# Pulser.net
KiCad netlist of a schematic drawn in Altium Designer
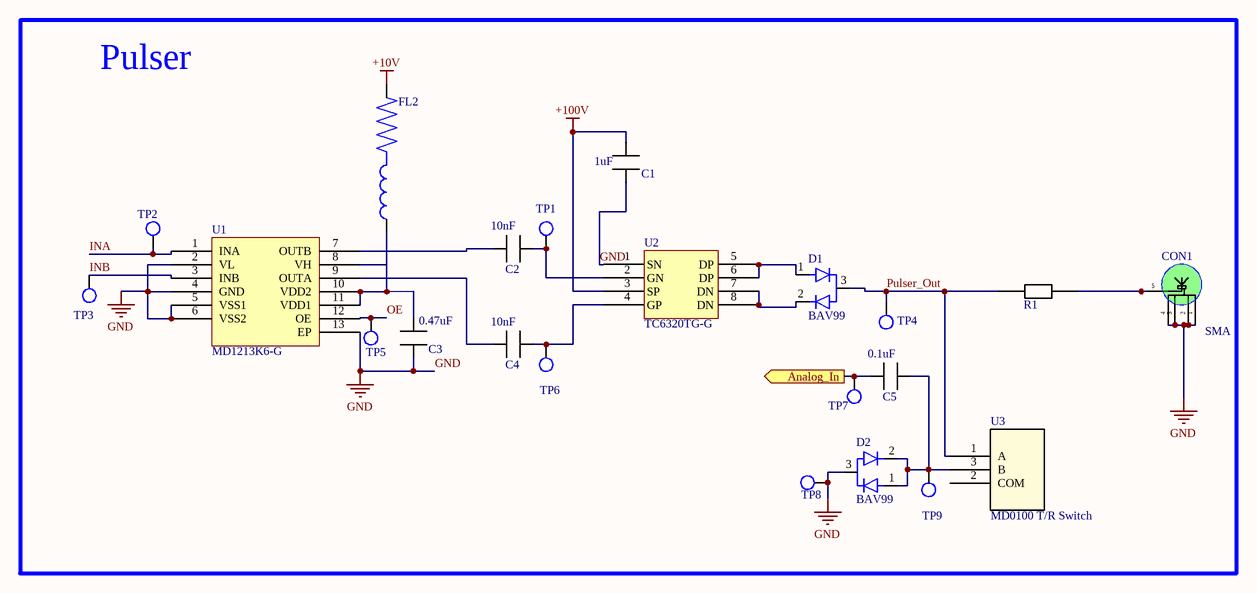
[diagram p0: Pulser.SchDoc]

(export (version "E")
  (design (tool "Eeschema 10.0.6"))
  (components
    (comp (ref "C1")
      (value "1uF")
      (footprint "CAP_1206")
      (description "CAP_1206")
      (fields (field (name "VAL") "1uF"))
      (libsource (lib "Passives") (part "CAP_1206"))
    )
    (comp (ref "C2")
      (value "10nF")
      (footprint "CAP_0805")
      (description "CAP_0805")
      (fields (field (name "VAL") "10nF"))
      (libsource (lib "Passives") (part "CAP_0805"))
    )
    (comp (ref "C3")
      (value "0.47uF")
      (footprint "CAP_0805")
      (description "CAP_0805")
      (fields (field (name "VAL") "0.47uF"))
      (libsource (lib "Passives") (part "CAP_0805"))
    )
    (comp (ref "C4")
      (value "10nF")
      (footprint "CAP_0805")
      (description "CAP_0805")
      (fields (field (name "VAL") "10nF"))
      (libsource (lib "Passives") (part "CAP_0805"))
    )
    (comp (ref "C5")
      (value "0.1uF")
      (footprint "CAP_0805")
      (description "CAP_0805")
      (fields (field (name "VAL") "0.1uF"))
      (libsource (lib "Passives") (part "CAP_0805"))
    )
    (comp (ref "CON1")
      (value "SMA")
      (footprint "A-SMA-KWE-15.1A")
      (libsource (lib "Connectors") (part "A-SMA-KWE-15.1A"))
    )
    (comp (ref "D1")
      (value "BAV99")
      (footprint "DIO_BAV99")
      (fields (field (name "MF") "ON Semiconductor"))
      (libsource (lib "Passives") (part "BAV99"))
    )
    (comp (ref "D2")
      (value "BAV99")
      (footprint "DIO_BAV99")
      (fields (field (name "MF") "ON Semiconductor"))
      (libsource (lib "Passives") (part "BAV99"))
    )
    (comp (ref "FL2")
      (value "~")
      (footprint "BEAD1206S601A40T")
      (fields (field (name "MF") "Murata") (field (name "MP") "BLM03EB500SZ1D"))
      (libsource (lib "Passives") (part "BEAD1206S601A40T"))
    )
    (comp (ref "R1")
      (value "200R")
      (footprint "RES_0805")
      (description "RES_0805")
      (libsource (lib "Passives") (part "RES_0805"))
    )
    (comp (ref "TP1") (value "TP") (footprint "CON_TP") (libsource (lib "Connectors") (part "Test_Point")))
    (comp (ref "TP2") (value "TP") (footprint "CON_TP") (libsource (lib "Connectors") (part "Test_Point")))
    (comp (ref "TP3") (value "TP") (footprint "CON_TP") (libsource (lib "Connectors") (part "Test_Point")))
    (comp (ref "TP4") (value "TP") (footprint "CON_TP") (libsource (lib "Connectors") (part "Test_Point")))
    (comp (ref "TP5") (value "TP") (footprint "CON_TP") (libsource (lib "Connectors") (part "Test_Point")))
    (comp (ref "TP6") (value "TP") (footprint "CON_TP") (libsource (lib "Connectors") (part "Test_Point")))
    (comp (ref "TP7") (value "TP") (footprint "CON_TP") (libsource (lib "Connectors") (part "Test_Point")))
    (comp (ref "TP8") (value "TP") (footprint "CON_TP") (libsource (lib "Connectors") (part "Test_Point")))
    (comp (ref "TP9") (value "TP") (footprint "CON_TP") (libsource (lib "Connectors") (part "Test_Point")))
    (comp (ref "U1")
      (value "MD1213K6-G")
      (footprint "QFN80P400X400X90-13N")
      (libsource (lib "IC_Digital") (part "MD1213K6-G"))
    )
    (comp (ref "U2")
      (value "TC6320TG-G")
      (footprint "SOIC127P600X175-8N")
      (libsource (lib "IC_Digital") (part "TC6320TG-G"))
    )
    (comp (ref "U3")
      (value "MD0100 T/R Switch")
      (footprint "TO-243AA_MCH")
      (description "Description")
      (fields
        (field (name "MANUFACTURER_PART_NUMBER") "MD0100N8-G")
        (field (name "COPYRIGHT") "Copyright (C) 2025 Ultra Librarian. All rights reserved.")
      )
      (libsource (lib "IC_Digital") (part "MD0100N8-G"))
    )
  )
  (nets
    (net (code "1") (name "+10V") (class "Default")
      (node (ref "FL2") (pin "2") (pinfunction "2_2") (pintype "passive"))
    )
    (net (code "2") (name "+100V") (class "Default")
      (node (ref "C1") (pin "2") (pinfunction "2_2") (pintype "passive"))
      (node (ref "U2") (pin "3") (pinfunction "SP_3") (pintype "passive"))
    )
    (net (code "3") (name "/Analog_In") (class "Default")
      (node (ref "C5") (pin "1") (pinfunction "1_1") (pintype "passive"))
      (node (ref "TP7") (pin "1") (pinfunction "A1_1") (pintype "passive"))
    )
    (net (code "4") (name "/INA") (class "Default")
      (node (ref "TP2") (pin "1") (pinfunction "A1_1") (pintype "passive"))
      (node (ref "U1") (pin "1") (pinfunction "INA_1") (pintype "passive"))
    )
    (net (code "5") (name "/INB") (class "Default")
      (node (ref "TP3") (pin "1") (pinfunction "A1_1") (pintype "passive"))
      (node (ref "U1") (pin "3") (pinfunction "INB_3") (pintype "passive"))
    )
    (net (code "6") (name "/OE") (class "Default")
      (node (ref "TP5") (pin "1") (pinfunction "A1_1") (pintype "passive"))
      (node (ref "U1") (pin "12") (pinfunction "OE_12") (pintype "passive"))
    )
    (net (code "7") (name "/Pulser_Out") (class "Default")
      (node (ref "D1") (pin "3") (pinfunction "3_3") (pintype "passive"))
      (node (ref "R1") (pin "1") (pinfunction "1_1") (pintype "passive"))
      (node (ref "TP4") (pin "1") (pinfunction "A1_1") (pintype "passive"))
      (node (ref "U3") (pin "1") (pinfunction "A_1") (pintype "passive"))
    )
    (net (code "8") (name "GND") (class "Default")
      (node (ref "C1") (pin "1") (pinfunction "1_1") (pintype "passive"))
      (node (ref "C3") (pin "2") (pinfunction "2_2") (pintype "passive"))
      (node (ref "CON1") (pin "1") (pinfunction "1_1") (pintype "passive"))
      (node (ref "CON1") (pin "2") (pinfunction "2_2") (pintype "passive"))
      (node (ref "CON1") (pin "3") (pinfunction "3_3") (pintype "passive"))
      (node (ref "CON1") (pin "4") (pinfunction "4_4") (pintype "passive"))
      (node (ref "D2") (pin "3") (pinfunction "3_3") (pintype "passive"))
      (node (ref "TP8") (pin "1") (pinfunction "A1_1") (pintype "passive"))
      (node (ref "U1") (pin "13") (pinfunction "EP_13") (pintype "power_in"))
      (node (ref "U1") (pin "2") (pinfunction "VL_2") (pintype "passive"))
      (node (ref "U1") (pin "4") (pinfunction "GND_4") (pintype "passive"))
      (node (ref "U1") (pin "5") (pinfunction "VSS1_5") (pintype "passive"))
      (node (ref "U1") (pin "6") (pinfunction "VSS2_6") (pintype "passive"))
      (node (ref "U2") (pin "1") (pinfunction "SN_1") (pintype "passive"))
    )
    (net (code "9") (name "Net-(CON1-Pad5)") (class "Default")
      (node (ref "CON1") (pin "5") (pinfunction "5_5") (pintype "passive"))
      (node (ref "R1") (pin "2") (pinfunction "2_2") (pintype "passive"))
    )
    (net (code "10") (name "Net-(D1-Pad1)") (class "Default")
      (node (ref "D1") (pin "1") (pinfunction "1_1") (pintype "passive"))
      (node (ref "U2") (pin "5") (pinfunction "DP_5") (pintype "passive"))
      (node (ref "U2") (pin "6") (pinfunction "DP_6") (pintype "passive"))
    )
    (net (code "11") (name "Net-(D1-Pad2)") (class "Default")
      (node (ref "D1") (pin "2") (pinfunction "2_2") (pintype "passive"))
      (node (ref "U2") (pin "7") (pinfunction "DN_7") (pintype "passive"))
      (node (ref "U2") (pin "8") (pinfunction "DN_8") (pintype "passive"))
    )
    (net (code "12") (name "Net-(TP1-A1)") (class "Default")
      (node (ref "C2") (pin "2") (pinfunction "2_2") (pintype "passive"))
      (node (ref "TP1") (pin "1") (pinfunction "A1_1") (pintype "passive"))
      (node (ref "U2") (pin "2") (pinfunction "GN_2") (pintype "passive"))
    )
    (net (code "13") (name "Net-(TP6-A1)") (class "Default")
      (node (ref "C4") (pin "2") (pinfunction "2_2") (pintype "passive"))
      (node (ref "TP6") (pin "1") (pinfunction "A1_1") (pintype "passive"))
      (node (ref "U2") (pin "4") (pinfunction "GP_4") (pintype "passive"))
    )
    (net (code "14") (name "Net-(TP9-A1)") (class "Default")
      (node (ref "C5") (pin "2") (pinfunction "2_2") (pintype "passive"))
      (node (ref "D2") (pin "1") (pinfunction "1_1") (pintype "passive"))
      (node (ref "D2") (pin "2") (pinfunction "2_2") (pintype "passive"))
      (node (ref "TP9") (pin "1") (pinfunction "A1_1") (pintype "passive"))
      (node (ref "U3") (pin "3") (pinfunction "B_3") (pintype "passive"))
    )
    (net (code "15") (name "Net-(U1-OUTA)") (class "Default")
      (node (ref "C4") (pin "1") (pinfunction "1_1") (pintype "passive"))
      (node (ref "U1") (pin "9") (pinfunction "OUTA_9") (pintype "passive"))
    )
    (net (code "16") (name "Net-(U1-OUTB)") (class "Default")
      (node (ref "C2") (pin "1") (pinfunction "1_1") (pintype "passive"))
      (node (ref "U1") (pin "7") (pinfunction "OUTB_7") (pintype "passive"))
    )
    (net (code "17") (name "Net-(U1-VDD1)") (class "Default")
      (node (ref "C3") (pin "1") (pinfunction "1_1") (pintype "passive"))
      (node (ref "FL2") (pin "1") (pinfunction "1_1") (pintype "passive"))
      (node (ref "U1") (pin "10") (pinfunction "VDD2_10") (pintype "passive"))
      (node (ref "U1") (pin "11") (pinfunction "VDD1_11") (pintype "passive"))
      (node (ref "U1") (pin "8") (pinfunction "VH_8") (pintype "passive"))
    )
    (net (code "18") (name "unconnected-(U3-COM-Pad2)") (class "Default")
      (node (ref "U3") (pin "2") (pinfunction "COM_2") (pintype "passive"))
    )
  )
)
